# Sheet3.net
KiCad netlist of a schematic drawn in Altium Designer
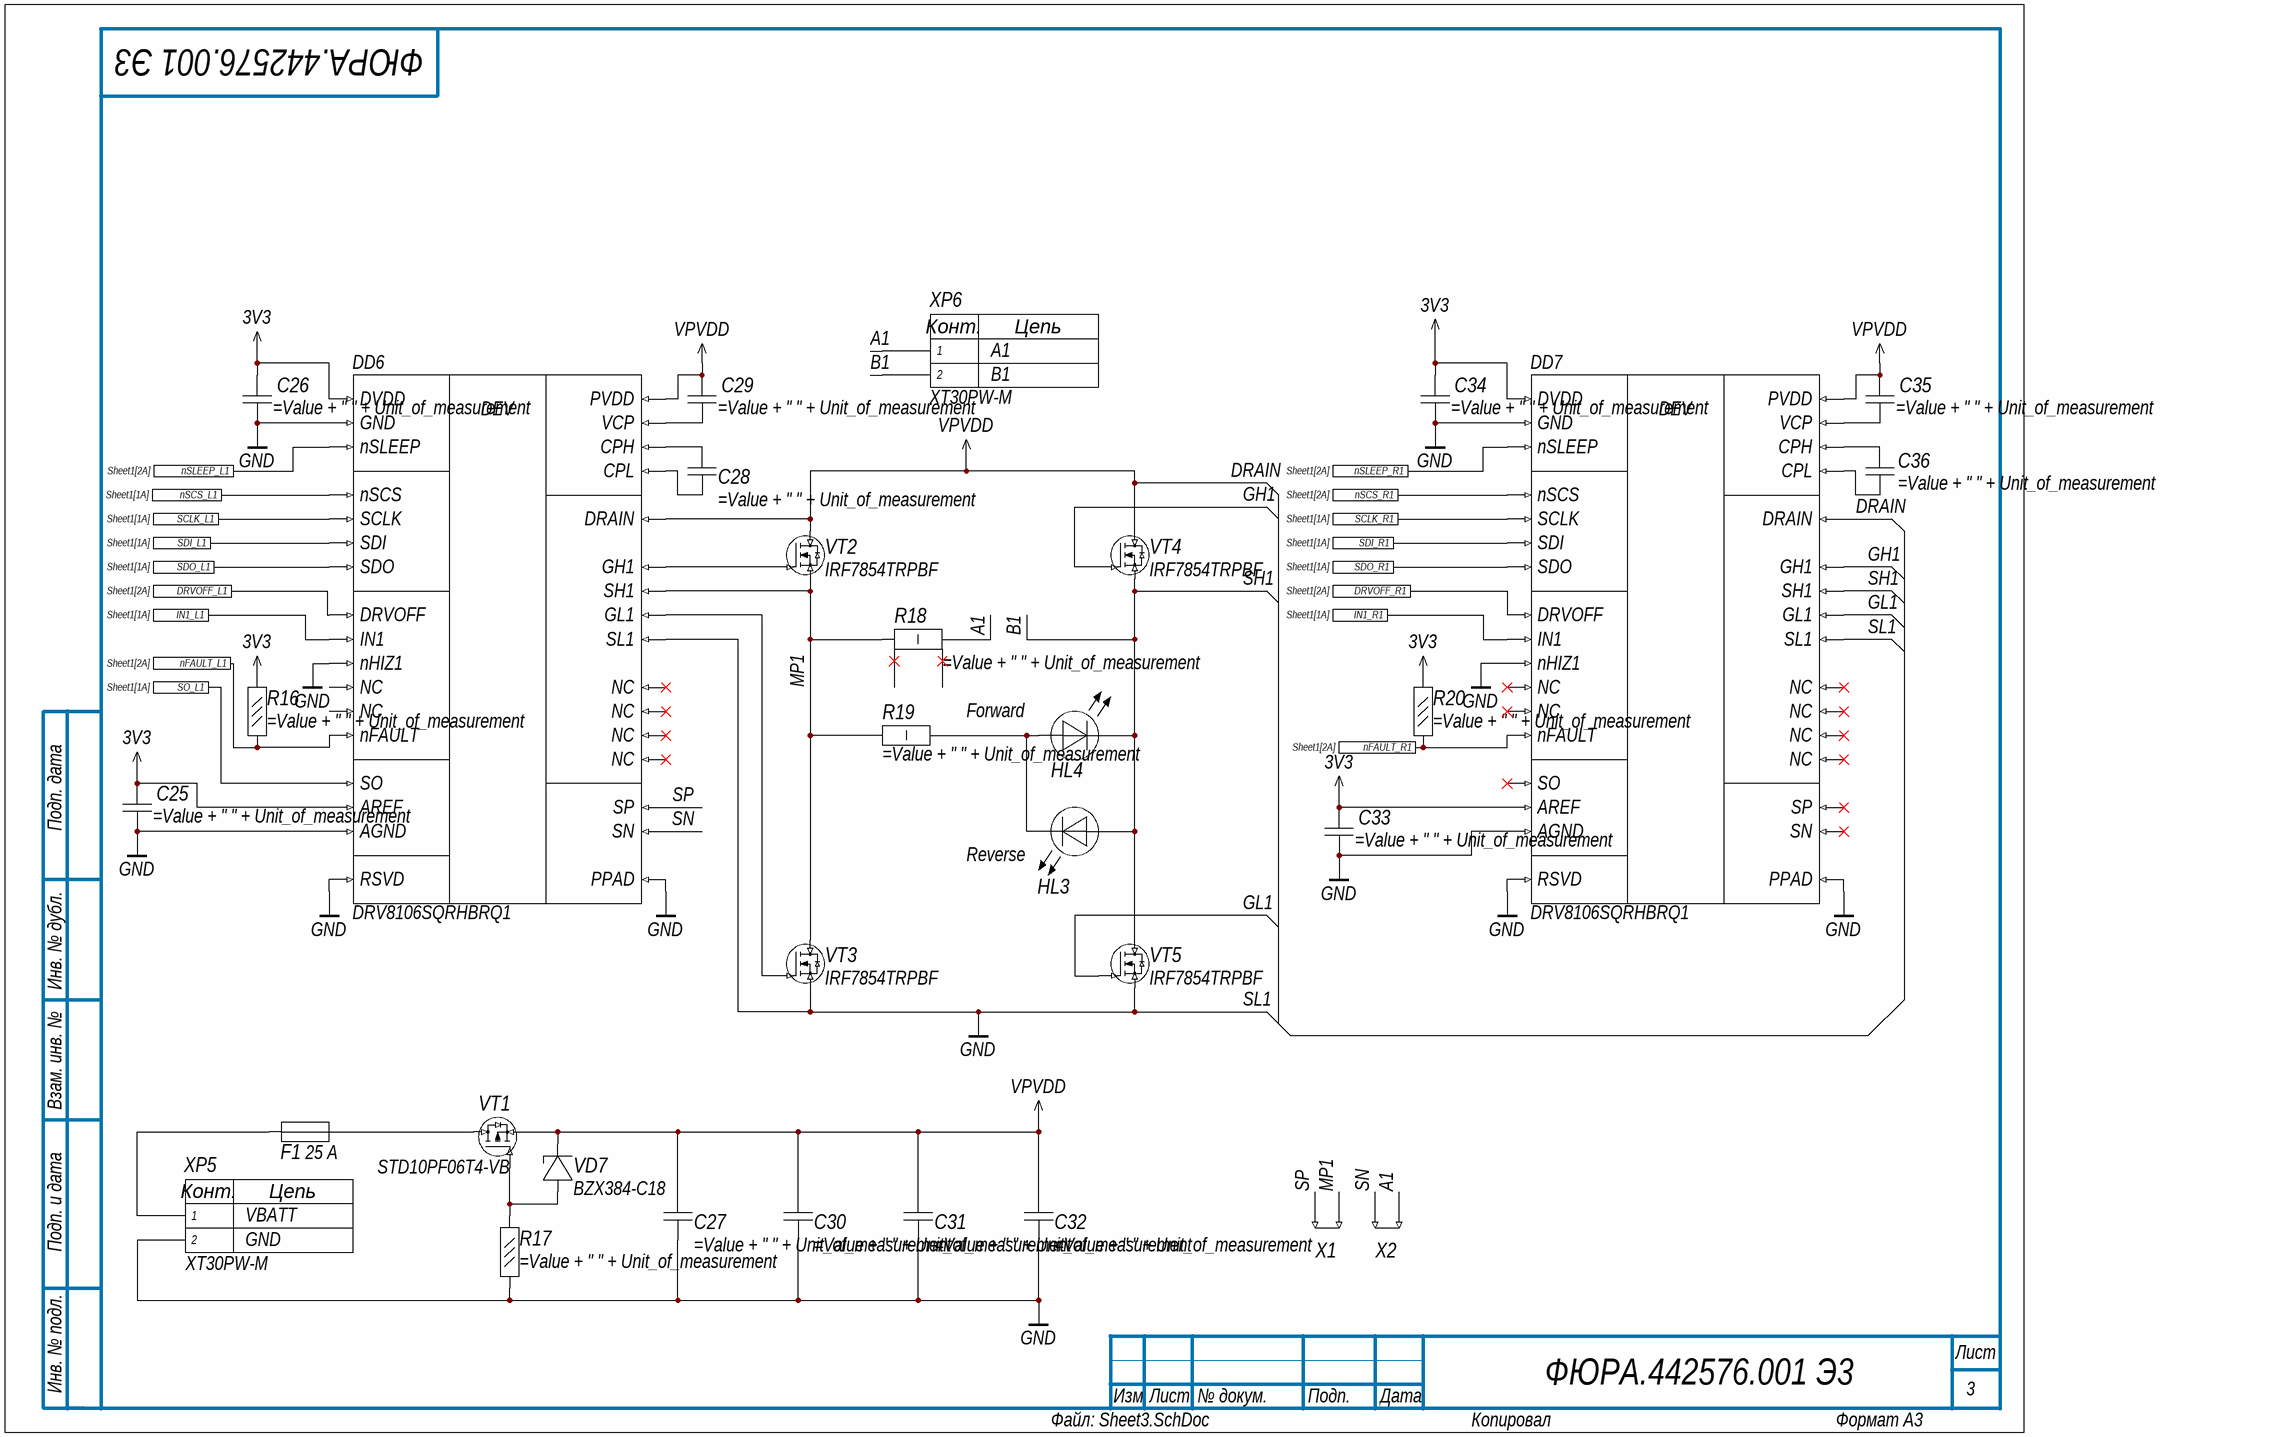
[diagram p0: Sheet3.SchDoc]

(export (version "E")
  (design (tool "Eeschema 10.0.6"))
  (components
    (comp (ref "C25")
      (value "1мкФ 6.3В")
      (footprint "CAP_0603")
      (description "Конденсатор керамический, типоразмера 0603")
      (libsource (lib "SimpleComponents") (part "CAP_0603"))
    )
    (comp (ref "C26")
      (value "1мкФ 6.3В")
      (footprint "CAP_0603")
      (description "Конденсатор керамический, типоразмера 0603")
      (libsource (lib "SimpleComponents") (part "CAP_0603"))
    )
    (comp (ref "C27")
      (value "0,1мкФ 50 В")
      (footprint "CAP_0603")
      (description "Конденсатор керамический, типоразмера 0603")
      (libsource (lib "SimpleComponents") (part "CAP_0603"))
    )
    (comp (ref "C28")
      (value "0,1мкФ 50 В")
      (footprint "CAP_0603")
      (description "Конденсатор керамический, типоразмера 0603")
      (libsource (lib "SimpleComponents") (part "CAP_0603"))
    )
    (comp (ref "C29")
      (value "1мкФ 16 В")
      (footprint "CAP_0603")
      (description "Конденсатор керамический, типоразмера 0603")
      (libsource (lib "SimpleComponents") (part "CAP_0603"))
    )
    (comp (ref "C30")
      (value "10мкФ 50В")
      (footprint "CAP_1206")
      (description "Конденсатор керамический, типоразмера 1206")
      (libsource (lib "SimpleComponents") (part "CAP_1206"))
    )
    (comp (ref "C31")
      (value "10мкФ 50В")
      (footprint "CAP_1206")
      (description "Конденсатор керамический, типоразмера 1206")
      (libsource (lib "SimpleComponents") (part "CAP_1206"))
    )
    (comp (ref "C32")
      (value "10мкФ 50В")
      (footprint "CAP_1206")
      (description "Конденсатор керамический, типоразмера 1206")
      (libsource (lib "SimpleComponents") (part "CAP_1206"))
    )
    (comp (ref "C33")
      (value "1мкФ 6.3В")
      (footprint "CAP_0603")
      (description "Конденсатор керамический, типоразмера 0603")
      (libsource (lib "SimpleComponents") (part "CAP_0603"))
    )
    (comp (ref "C34")
      (value "1мкФ 6.3В")
      (footprint "CAP_0603")
      (description "Конденсатор керамический, типоразмера 0603")
      (libsource (lib "SimpleComponents") (part "CAP_0603"))
    )
    (comp (ref "C35")
      (value "1мкФ 16 В")
      (footprint "CAP_0603")
      (description "Конденсатор керамический, типоразмера 0603")
      (libsource (lib "SimpleComponents") (part "CAP_0603"))
    )
    (comp (ref "C36")
      (value "0,1мкФ 50 В")
      (footprint "CAP_0603")
      (description "Конденсатор керамический, типоразмера 0603")
      (libsource (lib "SimpleComponents") (part "CAP_0603"))
    )
    (comp (ref "DD6")
      (value "DRV8106SQRHBRQ1")
      (footprint "VQFN32")
      (libsource (lib "ICs") (part "DRV8106SQRHBRQ1"))
    )
    (comp (ref "DD7")
      (value "DRV8106SQRHBRQ1")
      (footprint "VQFN32")
      (libsource (lib "ICs") (part "DRV8106SQRHBRQ1"))
    )
    (comp (ref "F1")
      (value "ва")
      (footprint "Fuse 5x20")
      (description "Предохранитель плавкий 5x20")
      (libsource (lib "SimpleComponents") (part "Fuse"))
    )
    (comp (ref "HL3") (value "3") (footprint "LED_0805") (libsource (lib "Complicated") (part "LED_0805")))
    (comp (ref "HL4") (value "3") (footprint "LED_0805") (libsource (lib "Complicated") (part "LED_0805")))
    (comp (ref "R16")
      (value "10кОм")
      (footprint "RES_0603")
      (description "Резистор, типоразмера 0603")
      (libsource (lib "SimpleComponents") (part "RES_0603"))
    )
    (comp (ref "R17")
      (value "10кОм")
      (footprint "RES_0603")
      (description "Резистор, типоразмера 0603")
      (libsource (lib "SimpleComponents") (part "RES_0603"))
    )
    (comp (ref "R18")
      (value "7.5мОм")
      (footprint "RES_2512")
      (description "Резистор, типоразмера 2512")
      (libsource (lib "SimpleComponents") (part "ResShunt_2512"))
    )
    (comp (ref "R19")
      (value "1.8кОм")
      (footprint "RES_2512")
      (description "Резистор, типоразмера 2512")
      (libsource (lib "SimpleComponents") (part "RES_2512"))
    )
    (comp (ref "R20")
      (value "10кОм")
      (footprint "RES_0603")
      (description "Резистор, типоразмера 0603")
      (libsource (lib "SimpleComponents") (part "RES_0603"))
    )
    (comp (ref "VD7")
      (value "BZX384-C18")
      (footprint "SOD-323")
      (description "Стабилитрон 18В 0.3Вт [SOD-323]")
      (libsource (lib "Complicated") (part "BZX384-C18"))
    )
    (comp (ref "VT1")
      (value "STD10PF06T4-VB")
      (footprint "DPAK_TO252")
      (description "Транзистор P-MOSFET 60В 30А 34Вт [D-PAK]")
      (libsource (lib "Complicated") (part "STD10PF06T4-VB"))
    )
    (comp (ref "VT2")
      (value "IRF7854TRPBF")
      (footprint "SOP-8 WithoutTP")
      (description "Транзистор, HEXFET, N-канал, 80В, 10А [SOIC-8]")
      (libsource (lib "Complicated") (part "IRF7854TRPBF"))
    )
    (comp (ref "VT3")
      (value "IRF7854TRPBF")
      (footprint "SOP-8 WithoutTP")
      (description "Транзистор, HEXFET, N-канал, 80В, 10А [SOIC-8]")
      (libsource (lib "Complicated") (part "IRF7854TRPBF"))
    )
    (comp (ref "VT4")
      (value "IRF7854TRPBF")
      (footprint "SOP-8 WithoutTP")
      (description "Транзистор, HEXFET, N-канал, 80В, 10А [SOIC-8]")
      (libsource (lib "Complicated") (part "IRF7854TRPBF"))
    )
    (comp (ref "VT5")
      (value "IRF7854TRPBF")
      (footprint "SOP-8 WithoutTP")
      (description "Транзистор, HEXFET, N-канал, 80В, 10А [SOIC-8]")
      (libsource (lib "Complicated") (part "IRF7854TRPBF"))
    )
    (comp (ref "X1")
      (value "Обозначение при заказе")
      (footprint "NetTie")
      (description "Описание свойств компонента")
      (libsource (lib "SimpleComponents") (part "NetTie"))
    )
    (comp (ref "X2")
      (value "Обозначение при заказе")
      (footprint "NetTie")
      (description "Описание свойств компонента")
      (libsource (lib "SimpleComponents") (part "NetTie"))
    )
    (comp (ref "XP5")
      (value "XT30PW-M")
      (footprint "XT30PW-M")
      (description "Socket; DC supply; XT30; male; PIN: 2; on PCBs; THT; yellow; 15A; 500V")
      (libsource (lib "SimpleComponents") (part "XT30PW-M"))
    )
    (comp (ref "XP6")
      (value "XT30PW-M")
      (footprint "XT30PW-M")
      (description "Socket; DC supply; XT30; male; PIN: 2; on PCBs; THT; yellow; 15A; 500V")
      (libsource (lib "SimpleComponents") (part "XT30PW-M"))
    )
  )
  (nets
    (net (code "2") (name "/A1") (class "Default")
      (node (ref "R18") (pin "1") (pinfunction "1_1") (pintype "passive"))
      (node (ref "X2") (pin "2") (pinfunction "2_2") (pintype "input"))
      (node (ref "XP6") (pin "1") (pinfunction "1_1") (pintype "passive"))
    )
    (net (code "3") (name "/B1") (class "Default")
      (node (ref "DD7") (pin "21") (pinfunction "SH1_21") (pintype "input"))
      (node (ref "HL3") (pin "A") (pinfunction "2_A") (pintype "passive"))
      (node (ref "HL4") (pin "C") (pinfunction "1_C") (pintype "passive"))
      (node (ref "VT4") (pin "2") (pinfunction "2_2") (pintype "input"))
      (node (ref "VT5") (pin "3") (pinfunction "3_3") (pintype "input"))
      (node (ref "XP6") (pin "2") (pinfunction "2_2") (pintype "passive"))
    )
    (net (code "4") (name "/DRVOFF_L1") (class "Default")
      (node (ref "DD6") (pin "12") (pinfunction "DRVOFF_12") (pintype "input"))
    )
    (net (code "5") (name "/DRVOFF_R1") (class "Default")
      (node (ref "DD7") (pin "12") (pinfunction "DRVOFF_12") (pintype "input"))
    )
    (net (code "6") (name "/GH1") (class "Default")
      (node (ref "DD7") (pin "20") (pinfunction "GH1_20") (pintype "input"))
      (node (ref "VT4") (pin "1") (pinfunction "1_1") (pintype "input"))
    )
    (net (code "7") (name "/GL1") (class "Default")
      (node (ref "DD7") (pin "22") (pinfunction "GL1_22") (pintype "input"))
      (node (ref "VT5") (pin "1") (pinfunction "1_1") (pintype "input"))
    )
    (net (code "8") (name "/IN1_L1") (class "Default")
      (node (ref "DD6") (pin "7") (pinfunction "IN1_7") (pintype "input"))
    )
    (net (code "9") (name "/IN1_R1") (class "Default")
      (node (ref "DD7") (pin "7") (pinfunction "IN1_7") (pintype "input"))
    )
    (net (code "10") (name "/MP1") (class "Default")
      (node (ref "DD6") (pin "21") (pinfunction "SH1_21") (pintype "input"))
      (node (ref "R18") (pin "2") (pinfunction "2_2") (pintype "passive"))
      (node (ref "R19") (pin "1") (pinfunction "1_1") (pintype "passive"))
      (node (ref "VT2") (pin "2") (pinfunction "2_2") (pintype "input"))
      (node (ref "VT3") (pin "3") (pinfunction "3_3") (pintype "input"))
      (node (ref "X1") (pin "2") (pinfunction "2_2") (pintype "input"))
    )
    (net (code "11") (name "/SCLK_L1") (class "Default")
      (node (ref "DD6") (pin "4") (pinfunction "SCLK_4") (pintype "input"))
    )
    (net (code "12") (name "/SCLK_R1") (class "Default")
      (node (ref "DD7") (pin "4") (pinfunction "SCLK_4") (pintype "input"))
    )
    (net (code "13") (name "/SDI_L1") (class "Default")
      (node (ref "DD6") (pin "5") (pinfunction "SDI_5") (pintype "input"))
    )
    (net (code "14") (name "/SDI_R1") (class "Default")
      (node (ref "DD7") (pin "5") (pinfunction "SDI_5") (pintype "input"))
    )
    (net (code "15") (name "/SDO_L1") (class "Default")
      (node (ref "DD6") (pin "6") (pinfunction "SDO_6") (pintype "input"))
    )
    (net (code "16") (name "/SDO_R1") (class "Default")
      (node (ref "DD7") (pin "6") (pinfunction "SDO_6") (pintype "input"))
    )
    (net (code "17") (name "/SN") (class "Default")
      (node (ref "DD6") (pin "19") (pinfunction "SN_19") (pintype "input"))
      (node (ref "X2") (pin "1") (pinfunction "1_1") (pintype "input"))
    )
    (net (code "18") (name "/SO_L1") (class "Default")
      (node (ref "DD6") (pin "14") (pinfunction "SO_14") (pintype "input"))
    )
    (net (code "19") (name "/SP") (class "Default")
      (node (ref "DD6") (pin "18") (pinfunction "SP_18") (pintype "input"))
      (node (ref "X1") (pin "1") (pinfunction "1_1") (pintype "input"))
    )
    (net (code "20") (name "/nFAULT_L1") (class "Default")
      (node (ref "DD6") (pin "13") (pinfunction "nFAULT_13") (pintype "input"))
      (node (ref "R16") (pin "1") (pinfunction "1_1") (pintype "passive"))
    )
    (net (code "21") (name "/nFAULT_R1") (class "Default")
      (node (ref "DD7") (pin "13") (pinfunction "nFAULT_13") (pintype "input"))
      (node (ref "R20") (pin "1") (pinfunction "1_1") (pintype "passive"))
    )
    (net (code "22") (name "/nSCS_L1") (class "Default")
      (node (ref "DD6") (pin "3") (pinfunction "nSCS_3") (pintype "input"))
    )
    (net (code "23") (name "/nSCS_R1") (class "Default")
      (node (ref "DD7") (pin "3") (pinfunction "nSCS_3") (pintype "input"))
    )
    (net (code "24") (name "/nSLEEP_L1") (class "Default")
      (node (ref "DD6") (pin "11") (pinfunction "nSLEEP_11") (pintype "input"))
    )
    (net (code "25") (name "/nSLEEP_R1") (class "Default")
      (node (ref "DD7") (pin "11") (pinfunction "nSLEEP_11") (pintype "input"))
    )
    (net (code "26") (name "3V3") (class "Default")
      (node (ref "C25") (pin "2") (pintype "passive"))
      (node (ref "C26") (pin "2") (pintype "passive"))
      (node (ref "C33") (pin "2") (pintype "passive"))
      (node (ref "C34") (pin "2") (pintype "passive"))
      (node (ref "DD6") (pin "16") (pinfunction "AREF_16") (pintype "input"))
      (node (ref "DD6") (pin "2") (pinfunction "DVDD_2") (pintype "input"))
      (node (ref "DD7") (pin "16") (pinfunction "AREF_16") (pintype "input"))
      (node (ref "DD7") (pin "2") (pinfunction "DVDD_2") (pintype "input"))
      (node (ref "R16") (pin "2") (pinfunction "2_2") (pintype "passive"))
      (node (ref "R20") (pin "2") (pinfunction "2_2") (pintype "passive"))
    )
    (net (code "27") (name "GND") (class "Default")
      (node (ref "C25") (pin "1") (pintype "passive"))
      (node (ref "C26") (pin "1") (pintype "passive"))
      (node (ref "C27") (pin "1") (pintype "passive"))
      (node (ref "C30") (pin "1") (pintype "passive"))
      (node (ref "C31") (pin "1") (pintype "passive"))
      (node (ref "C32") (pin "1") (pintype "passive"))
      (node (ref "C33") (pin "1") (pintype "passive"))
      (node (ref "C34") (pin "1") (pintype "passive"))
      (node (ref "DD6") (pin "0") (pinfunction "PPAD_0") (pintype "input"))
      (node (ref "DD6") (pin "1") (pinfunction "GND_1") (pintype "input"))
      (node (ref "DD6") (pin "15") (pinfunction "RSVD_15") (pintype "input"))
      (node (ref "DD6") (pin "17") (pinfunction "AGND_17") (pintype "input"))
      (node (ref "DD6") (pin "23") (pinfunction "SL1_23") (pintype "input"))
      (node (ref "DD6") (pin "8") (pinfunction "nHIZ1_8") (pintype "input"))
      (node (ref "DD7") (pin "0") (pinfunction "PPAD_0") (pintype "input"))
      (node (ref "DD7") (pin "1") (pinfunction "GND_1") (pintype "input"))
      (node (ref "DD7") (pin "15") (pinfunction "RSVD_15") (pintype "input"))
      (node (ref "DD7") (pin "17") (pinfunction "AGND_17") (pintype "input"))
      (node (ref "DD7") (pin "23") (pinfunction "SL1_23") (pintype "input"))
      (node (ref "DD7") (pin "8") (pinfunction "nHIZ1_8") (pintype "input"))
      (node (ref "R17") (pin "1") (pinfunction "1_1") (pintype "passive"))
      (node (ref "VT3") (pin "2") (pinfunction "2_2") (pintype "input"))
      (node (ref "VT5") (pin "2") (pinfunction "2_2") (pintype "input"))
      (node (ref "XP5") (pin "2") (pinfunction "2_2") (pintype "passive"))
    )
    (net (code "28") (name "Net-(DD6-CPH)") (class "Default")
      (node (ref "C28") (pin "2") (pintype "passive"))
      (node (ref "DD6") (pin "31") (pinfunction "CPH_31") (pintype "input"))
    )
    (net (code "29") (name "Net-(DD6-CPL)") (class "Default")
      (node (ref "C28") (pin "1") (pintype "passive"))
      (node (ref "DD6") (pin "32") (pinfunction "CPL_32") (pintype "input"))
    )
    (net (code "30") (name "Net-(DD6-GH1)") (class "Default")
      (node (ref "DD6") (pin "20") (pinfunction "GH1_20") (pintype "input"))
      (node (ref "VT2") (pin "1") (pinfunction "1_1") (pintype "input"))
    )
    (net (code "31") (name "Net-(DD6-GL1)") (class "Default")
      (node (ref "DD6") (pin "22") (pinfunction "GL1_22") (pintype "input"))
      (node (ref "VT3") (pin "1") (pinfunction "1_1") (pintype "input"))
    )
    (net (code "32") (name "Net-(DD6-VCP)") (class "Default")
      (node (ref "C29") (pin "1") (pintype "passive"))
      (node (ref "DD6") (pin "30") (pinfunction "VCP_30") (pintype "input"))
    )
    (net (code "33") (name "Net-(DD7-CPH)") (class "Default")
      (node (ref "C36") (pin "2") (pintype "passive"))
      (node (ref "DD7") (pin "31") (pinfunction "CPH_31") (pintype "input"))
    )
    (net (code "34") (name "Net-(DD7-CPL)") (class "Default")
      (node (ref "C36") (pin "1") (pintype "passive"))
      (node (ref "DD7") (pin "32") (pinfunction "CPL_32") (pintype "input"))
    )
    (net (code "35") (name "Net-(DD7-VCP)") (class "Default")
      (node (ref "C35") (pin "1") (pintype "passive"))
      (node (ref "DD7") (pin "30") (pinfunction "VCP_30") (pintype "input"))
    )
    (net (code "36") (name "Net-(F1-Pad1)") (class "Default")
      (node (ref "F1") (pin "1") (pinfunction "1_1") (pintype "passive"))
      (node (ref "XP5") (pin "1") (pinfunction "1_1") (pintype "passive"))
    )
    (net (code "37") (name "Net-(HL3-1)") (class "Default")
      (node (ref "HL3") (pin "C") (pinfunction "1_C") (pintype "passive"))
      (node (ref "HL4") (pin "A") (pinfunction "2_A") (pintype "passive"))
      (node (ref "R19") (pin "2") (pinfunction "2_2") (pintype "passive"))
    )
    (net (code "38") (name "Net-(VT1-D)") (class "Default")
      (node (ref "F1") (pin "2") (pinfunction "2_2") (pintype "passive"))
      (node (ref "VT1") (pin "4") (pinfunction "D_4") (pintype "input"))
    )
    (net (code "39") (name "Net-(VT1-G)") (class "Default")
      (node (ref "R17") (pin "2") (pinfunction "2_2") (pintype "passive"))
      (node (ref "VD7") (pin "2") (pinfunction "2_2") (pintype "passive"))
      (node (ref "VT1") (pin "1") (pinfunction "G_1") (pintype "input"))
    )
    (net (code "40") (name "VPVDD") (class "Default")
      (node (ref "C27") (pin "2") (pintype "passive"))
      (node (ref "C29") (pin "2") (pintype "passive"))
      (node (ref "C30") (pin "2") (pintype "passive"))
      (node (ref "C31") (pin "2") (pintype "passive"))
      (node (ref "C32") (pin "2") (pintype "passive"))
      (node (ref "C35") (pin "2") (pintype "passive"))
      (node (ref "DD6") (pin "28") (pinfunction "DRAIN_28") (pintype "input"))
      (node (ref "DD6") (pin "29") (pinfunction "PVDD_29") (pintype "input"))
      (node (ref "DD7") (pin "28") (pinfunction "DRAIN_28") (pintype "input"))
      (node (ref "DD7") (pin "29") (pinfunction "PVDD_29") (pintype "input"))
      (node (ref "VD7") (pin "1") (pinfunction "1_1") (pintype "passive"))
      (node (ref "VT1") (pin "3") (pinfunction "S_3") (pintype "input"))
      (node (ref "VT2") (pin "3") (pinfunction "3_3") (pintype "input"))
      (node (ref "VT4") (pin "3") (pinfunction "3_3") (pintype "input"))
    )
    (net (code "41") (name "unconnected-(DD6-NC-Pad9)") (class "Default")
      (node (ref "DD6") (pin "9") (pinfunction "NC_9") (pintype "input"))
    )
    (net (code "42") (name "unconnected-(DD6-NC-Pad10)") (class "Default")
      (node (ref "DD6") (pin "10") (pinfunction "NC_10") (pintype "input"))
    )
    (net (code "43") (name "unconnected-(DD6-NC-Pad24)") (class "Default")
      (node (ref "DD6") (pin "24") (pinfunction "NC_24") (pintype "input+no_connect"))
    )
    (net (code "44") (name "unconnected-(DD6-NC-Pad25)") (class "Default")
      (node (ref "DD6") (pin "25") (pinfunction "NC_25") (pintype "input+no_connect"))
    )
    (net (code "45") (name "unconnected-(DD6-NC-Pad26)") (class "Default")
      (node (ref "DD6") (pin "26") (pinfunction "NC_26") (pintype "input+no_connect"))
    )
    (net (code "46") (name "unconnected-(DD6-NC-Pad27)") (class "Default")
      (node (ref "DD6") (pin "27") (pinfunction "NC_27") (pintype "input+no_connect"))
    )
    (net (code "47") (name "unconnected-(DD7-NC-Pad9)") (class "Default")
      (node (ref "DD7") (pin "9") (pinfunction "NC_9") (pintype "input+no_connect"))
    )
    (net (code "48") (name "unconnected-(DD7-NC-Pad10)") (class "Default")
      (node (ref "DD7") (pin "10") (pinfunction "NC_10") (pintype "input+no_connect"))
    )
    (net (code "49") (name "unconnected-(DD7-NC-Pad24)") (class "Default")
      (node (ref "DD7") (pin "24") (pinfunction "NC_24") (pintype "input+no_connect"))
    )
    (net (code "50") (name "unconnected-(DD7-NC-Pad25)") (class "Default")
      (node (ref "DD7") (pin "25") (pinfunction "NC_25") (pintype "input+no_connect"))
    )
    (net (code "51") (name "unconnected-(DD7-NC-Pad26)") (class "Default")
      (node (ref "DD7") (pin "26") (pinfunction "NC_26") (pintype "input+no_connect"))
    )
    (net (code "52") (name "unconnected-(DD7-NC-Pad27)") (class "Default")
      (node (ref "DD7") (pin "27") (pinfunction "NC_27") (pintype "input+no_connect"))
    )
    (net (code "53") (name "unconnected-(DD7-SN-Pad19)") (class "Default")
      (node (ref "DD7") (pin "19") (pinfunction "SN_19") (pintype "input+no_connect"))
    )
    (net (code "54") (name "unconnected-(DD7-SO-Pad14)") (class "Default")
      (node (ref "DD7") (pin "14") (pinfunction "SO_14") (pintype "input+no_connect"))
    )
    (net (code "55") (name "unconnected-(DD7-SP-Pad18)") (class "Default")
      (node (ref "DD7") (pin "18") (pinfunction "SP_18") (pintype "input+no_connect"))
    )
    (net (code "56") (name "unconnected-(R18-Pad1)") (class "Default")
      (node (ref "R18") (pin "1") (pinfunction "1_1") (pintype "passive+no_connect"))
    )
    (net (code "57") (name "unconnected-(R18-Pad2)") (class "Default")
      (node (ref "R18") (pin "2") (pinfunction "2_2") (pintype "passive+no_connect"))
    )
  )
)
